# water_buzzer.net
KiCad netlist of a schematic drawn in EAGLE
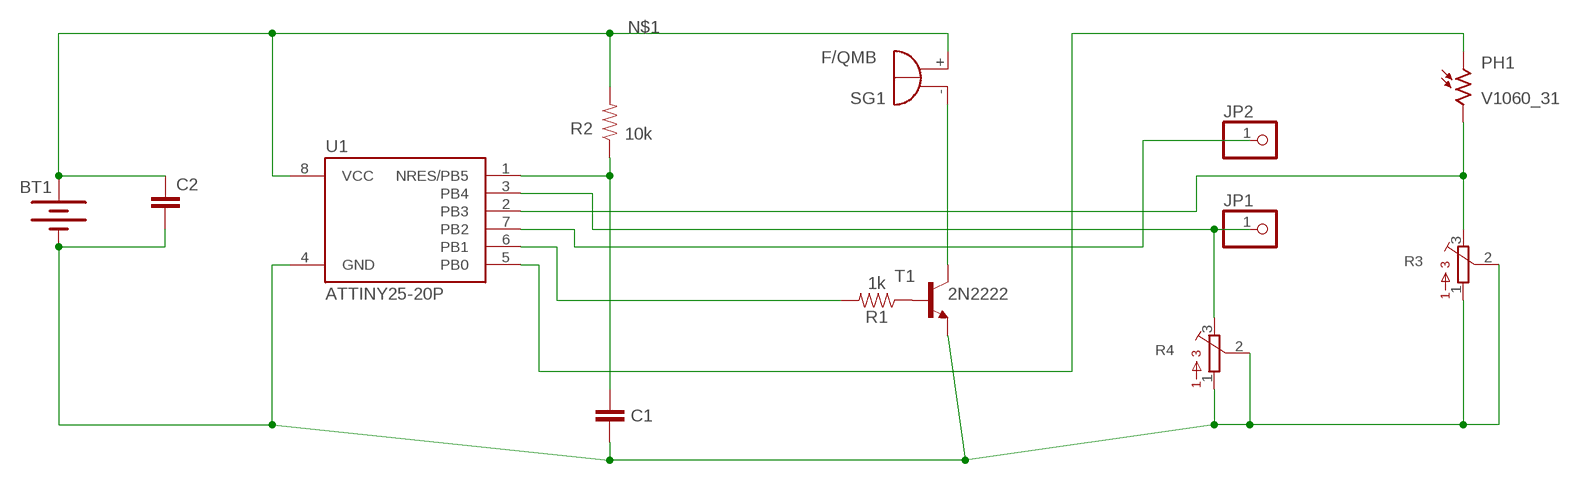
[diagram p0: schematic, sheet 1]

(export (version "E")
  (design (tool "Eeschema 10.0.6"))
  (components
    (comp (ref "BT1")
      (value "BATTERY-20MM_PTH")
      (footprint "eagle-import:BATTCOM_20MM_PTH")
      (libsource (lib "eagle-import") (part "BATTERY-20MM_PTH"))
    )
    (comp (ref "C1")
      (value "C5/2.5")
      (footprint "eagle-import:C5B2.5")
      (libsource (lib "eagle-import") (part "C5/2.5"))
    )
    (comp (ref "C2")
      (value "C5/2.5")
      (footprint "eagle-import:C5B2.5")
      (libsource (lib "eagle-import") (part "C5/2.5"))
    )
    (comp (ref "JP1")
      (value "PINHD-1X1")
      (footprint "eagle-import:1X01")
      (libsource (lib "eagle-import") (part "PINHD-1X1"))
    )
    (comp (ref "JP2")
      (value "PINHD-1X1")
      (footprint "eagle-import:1X01")
      (libsource (lib "eagle-import") (part "PINHD-1X1"))
    )
    (comp (ref "PH1")
      (value "V1060_31")
      (footprint "eagle-import:TO-5_V10")
      (libsource (lib "eagle-import") (part "?1060V_31"))
    )
    (comp (ref "R1")
      (value "1k")
      (footprint "eagle-import:AXIAL-0.3")
      (libsource (lib "eagle-import") (part "1KOHM-HORIZ-1/4W-5%"))
    )
    (comp (ref "R2")
      (value "10k")
      (footprint "eagle-import:AXIAL-0.3")
      (libsource (lib "eagle-import") (part "10KOHM-HORIZ-1/4W-5%"))
    )
    (comp (ref "R3")
      (value "3362R")
      (footprint "eagle-import:3362R")
      (libsource (lib "eagle-import") (part "3362R"))
    )
    (comp (ref "R4")
      (value "3362R")
      (footprint "eagle-import:3362R")
      (libsource (lib "eagle-import") (part "3362R"))
    )
    (comp (ref "SG1")
      (value "F/QMB")
      (footprint "eagle-import:F_QMB")
      (libsource (lib "eagle-import") (part "F/QMB"))
    )
    (comp (ref "T1")
      (value "2N2222")
      (footprint "eagle-import:TO92-EBC-OVAL")
      (libsource (lib "eagle-import") (part "2N2222"))
    )
    (comp (ref "U1")
      (value "ATTINY25-20P")
      (footprint "eagle-import:PDIP08_300MIL")
      (libsource (lib "eagle-import") (part "ATTINY25P-20"))
    )
  )
  (nets
    (net (code "1") (name "/N$1") (class "Default")
      (node (ref "BT1") (pin "1") (pinfunction "+_1") (pintype "power_in"))
      (node (ref "C2") (pin "1") (pinfunction "1_1") (pintype "passive"))
      (node (ref "R2") (pin "P$2") (pinfunction "2_P$2") (pintype "passive"))
      (node (ref "SG1") (pin "+") (pinfunction "-_+") (pintype "passive"))
      (node (ref "U1") (pin "8") (pinfunction "VCC_8") (pintype "power_in"))
    )
    (net (code "2") (name "Net-(BT1--)") (class "Default")
      (node (ref "BT1") (pin "2") (pinfunction "-_2") (pintype "power_in"))
      (node (ref "C1") (pin "1") (pinfunction "1_1") (pintype "passive"))
      (node (ref "C2") (pin "2") (pinfunction "2_2") (pintype "passive"))
      (node (ref "R3") (pin "1") (pinfunction "1_1") (pintype "passive"))
      (node (ref "R3") (pin "2") (pinfunction "2_2") (pintype "passive"))
      (node (ref "R4") (pin "1") (pinfunction "1_1") (pintype "passive"))
      (node (ref "R4") (pin "2") (pinfunction "2_2") (pintype "passive"))
      (node (ref "T1") (pin "E") (pinfunction "E_E") (pintype "passive"))
      (node (ref "U1") (pin "4") (pinfunction "GND_4") (pintype "power_in"))
    )
    (net (code "3") (name "Net-(R1-1)") (class "Default")
      (node (ref "R1") (pin "P$1") (pinfunction "1_P$1") (pintype "passive"))
      (node (ref "T1") (pin "B") (pinfunction "B_B") (pintype "passive"))
    )
    (net (code "4") (name "Net-(R1-2)") (class "Default")
      (node (ref "R1") (pin "P$2") (pinfunction "2_P$2") (pintype "passive"))
      (node (ref "U1") (pin "6") (pinfunction "PB1_6") (pintype "bidirectional"))
    )
    (net (code "5") (name "Net-(R2-1)") (class "Default")
      (node (ref "C1") (pin "2") (pinfunction "2_2") (pintype "passive"))
      (node (ref "R2") (pin "P$1") (pinfunction "1_P$1") (pintype "passive"))
      (node (ref "U1") (pin "1") (pinfunction "NRES/PB5_1") (pintype "bidirectional"))
    )
    (net (code "6") (name "Net-(SG1-+)") (class "Default")
      (node (ref "SG1") (pin "-") (pinfunction "+_-") (pintype "passive"))
      (node (ref "T1") (pin "C") (pinfunction "C_C") (pintype "passive"))
    )
    (net (code "7") (name "Net-(U1-PB0)") (class "Default")
      (node (ref "PH1") (pin "1") (pinfunction "1_1") (pintype "passive"))
      (node (ref "U1") (pin "5") (pinfunction "PB0_5") (pintype "bidirectional"))
    )
    (net (code "8") (name "Net-(U1-PB2)") (class "Default")
      (node (ref "JP2") (pin "1") (pinfunction "1_1") (pintype "passive"))
      (node (ref "U1") (pin "7") (pinfunction "PB2_7") (pintype "bidirectional"))
    )
    (net (code "9") (name "Net-(U1-PB3)") (class "Default")
      (node (ref "PH1") (pin "2") (pinfunction "2_2") (pintype "passive"))
      (node (ref "R3") (pin "3") (pinfunction "3_3") (pintype "passive"))
      (node (ref "U1") (pin "2") (pinfunction "PB3_2") (pintype "bidirectional"))
    )
    (net (code "10") (name "Net-(U1-PB4)") (class "Default")
      (node (ref "JP1") (pin "1") (pinfunction "1_1") (pintype "passive"))
      (node (ref "R4") (pin "3") (pinfunction "3_3") (pintype "passive"))
      (node (ref "U1") (pin "3") (pinfunction "PB4_3") (pintype "bidirectional"))
    )
  )
)
